# ifly_watch.net
KiCad netlist of a schematic drawn in Altium Designer
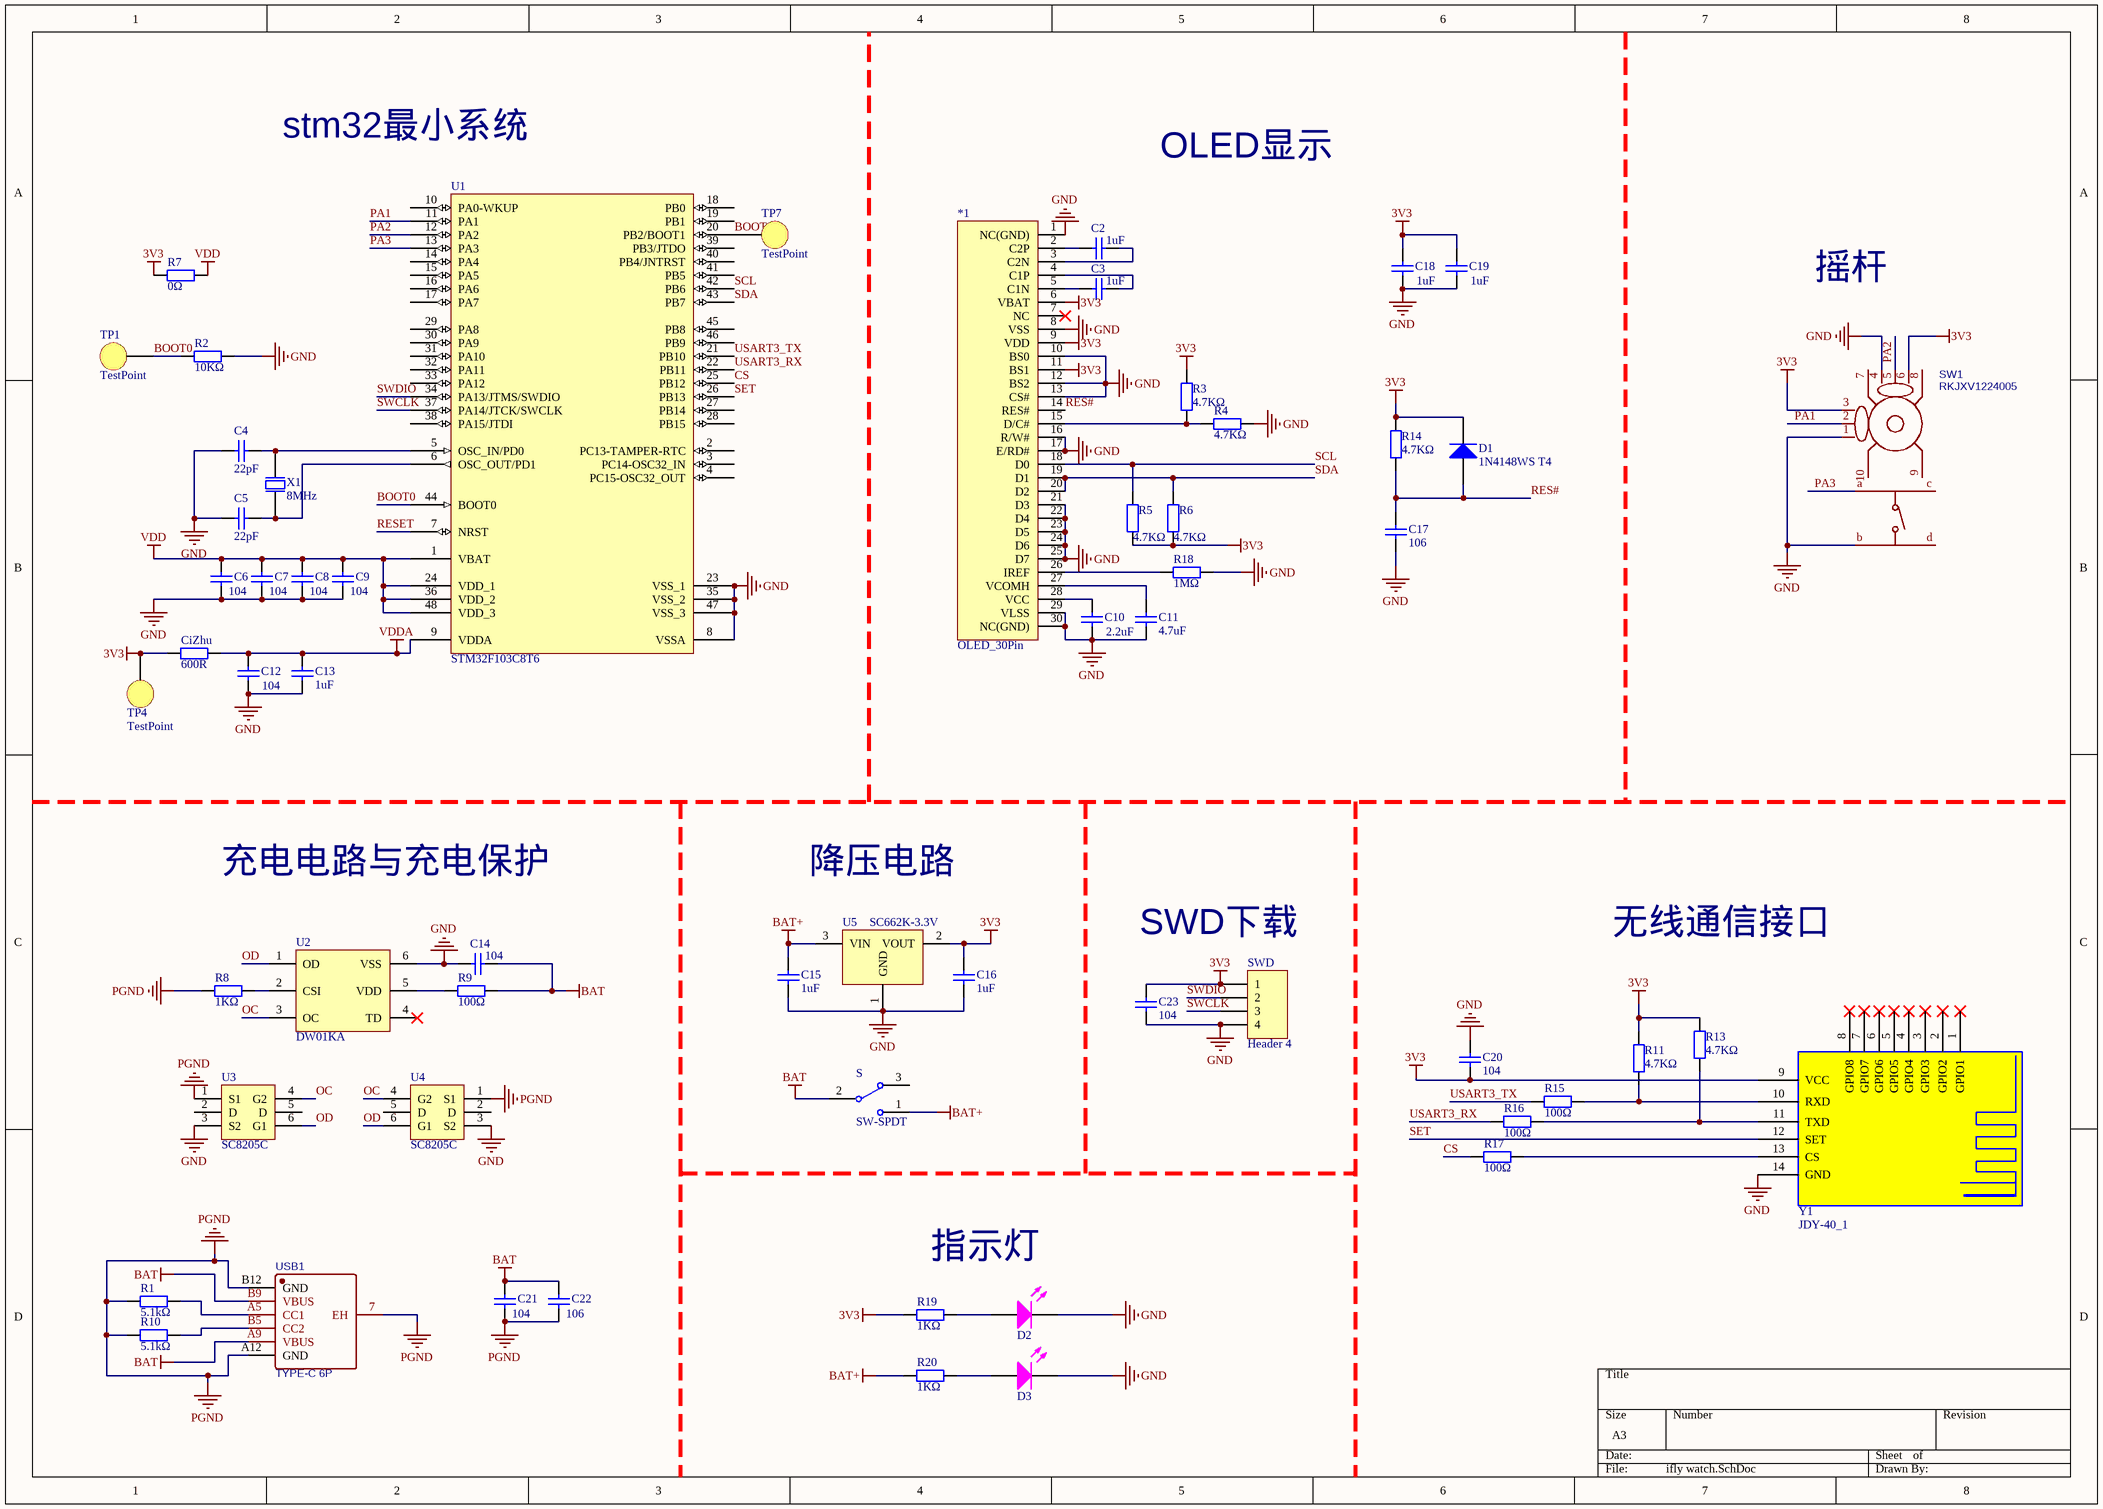
[diagram p0: ifly watch.SchDoc]

(export (version "E")
  (design (tool "Eeschema 10.0.6"))
  (components
    (comp (ref "*1")
      (value "OLED_30Pin")
      (footprint "OLED_0.96-30P-P0.70-12864")
      (libsource (lib "CQL_SchLib") (part "OLED_30Pin"))
    )
    (comp (ref "C2")
      (value "1uF")
      (footprint "LC-0603_C")
      (description "贴片电容")
      (libsource (lib "RobotLab") (part "0603 1uF (105) 10% 50V"))
    )
    (comp (ref "C3")
      (value "1uF")
      (footprint "LC-0603_C")
      (description "贴片电容")
      (libsource (lib "RobotLab") (part "0603 1uF (105) 10% 50V"))
    )
    (comp (ref "C4")
      (value "22pF")
      (footprint "C0603")
      (description "Polarized Capacitor (Radial)")
      (fields (field (name "Comment") "20pf") (field (name "PUBLISHER") "Altium Limited"))
      (libsource (lib "电容") (part "Cap Chip 0805"))
    )
    (comp (ref "C5")
      (value "22pF")
      (footprint "C0603")
      (description "Polarized Capacitor (Radial)")
      (fields (field (name "PUBLISHER") "Altium Limited"))
      (libsource (lib "电容") (part "Cap Chip 0805"))
    )
    (comp (ref "C6")
      (value "104")
      (footprint "LC-0603_C")
      (description "贴片电容")
      (libsource (lib "RobotLab") (part "0603 100nF (104) 10% 50V"))
    )
    (comp (ref "C7")
      (value "104")
      (footprint "LC-0603_C")
      (description "贴片电容")
      (libsource (lib "RobotLab") (part "0603 100nF (104) 10% 50V"))
    )
    (comp (ref "C8")
      (value "104")
      (footprint "LC-0603_C")
      (description "贴片电容")
      (libsource (lib "RobotLab") (part "0603 100nF (104) 10% 50V"))
    )
    (comp (ref "C9")
      (value "104")
      (footprint "LC-0603_C")
      (description "贴片电容")
      (libsource (lib "RobotLab") (part "0603 100nF (104) 10% 50V"))
    )
    (comp (ref "C10")
      (value "2.2uF")
      (footprint "LC-0603_C")
      (description "贴片电容")
      (libsource (lib "RobotLab") (part "0603 2.2uF (225) 10% 16V"))
    )
    (comp (ref "C11")
      (value "4.7uF")
      (footprint "LC-0603_C")
      (description "贴片电容")
      (libsource (lib "RobotLab") (part "0603 4.7uF (475) 10% 16V"))
    )
    (comp (ref "C12")
      (value "104")
      (footprint "LC-0603_C")
      (description "贴片电容")
      (libsource (lib "RobotLab") (part "0603 100nF (104) 10% 50V"))
    )
    (comp (ref "C13")
      (value "1uF")
      (footprint "LC-0603_C")
      (description "贴片电容")
      (libsource (lib "RobotLab") (part "0603 1uF (105) 10% 50V"))
    )
    (comp (ref "C14")
      (value "104")
      (footprint "LC-0603_C")
      (description "贴片电容")
      (libsource (lib "RobotLab") (part "0603 100nF (104) 10% 50V"))
    )
    (comp (ref "C15")
      (value "1uF")
      (footprint "LC-0603_C")
      (description "贴片电容")
      (libsource (lib "RobotLab") (part "0603 1uF (105) 10% 50V"))
    )
    (comp (ref "C16")
      (value "1uF")
      (footprint "LC-0603_C")
      (description "贴片电容")
      (libsource (lib "RobotLab") (part "0603 1uF (105) 10% 50V"))
    )
    (comp (ref "C17")
      (value "106")
      (footprint "LC-0603_C")
      (description "贴片电容")
      (libsource (lib "RobotLab") (part "0603 10uF (106) 10% 10V"))
    )
    (comp (ref "C18")
      (value "1uF")
      (footprint "LC-0603_C")
      (description "贴片电容")
      (libsource (lib "RobotLab") (part "0603 1uF (105) 10% 50V"))
    )
    (comp (ref "C19")
      (value "1uF")
      (footprint "LC-0603_C")
      (description "贴片电容")
      (libsource (lib "RobotLab") (part "0603 1uF (105) 10% 50V"))
    )
    (comp (ref "C20")
      (value "104")
      (footprint "LC-0603_C")
      (description "贴片电容")
      (libsource (lib "RobotLab") (part "0603 100nF (104) 10% 50V"))
    )
    (comp (ref "C21")
      (value "104")
      (footprint "LC-0603_C")
      (description "贴片电容")
      (libsource (lib "RobotLab") (part "0603 100nF (104) 10% 50V"))
    )
    (comp (ref "C22")
      (value "106")
      (footprint "LC-0603_C")
      (description "贴片电容")
      (libsource (lib "RobotLab") (part "0603 1uF (105) 10% 50V"))
    )
    (comp (ref "C23")
      (value "104")
      (footprint "LC-0603_C")
      (description "Polarized Capacitor (Radial)")
      (fields (field (name "PUBLISHER") "Altium Limited"))
      (libsource (lib "电容") (part "Cap Chip 0603"))
    )
    (comp (ref "CiZhu")
      (value "600R")
      (footprint "0603_R")
      (description "电阻_磁珠")
      (libsource (lib "CQL_SchLib") (part "Cizhu"))
    )
    (comp (ref "D1")
      (value "1N4148WS T4")
      (footprint "LC-SOD-323")
      (description "二极管")
      (libsource (lib "RobotLab") (part "SOD-323 1N4148WS T4"))
    )
    (comp (ref "D2")
      (value "0603")
      (footprint "LED0603 R")
      (description "Typical INFRARED GaAs LED")
      (fields (field (name "PUBLISHER") "Altium Limited"))
      (libsource (lib "光电显示器件") (part "LED-3-R"))
    )
    (comp (ref "D3")
      (value "0603")
      (footprint "LED0603 R")
      (description "Typical INFRARED GaAs LED")
      (fields (field (name "PUBLISHER") "Altium Limited"))
      (libsource (lib "光电显示器件") (part "LED-3-R"))
    )
    (comp (ref "R1")
      (value "5.1kΩ")
      (footprint "LC-0603_R")
      (description "贴片电阻")
      (libsource (lib "RobotLab") (part "0603 100Ω (1000) 1%"))
    )
    (comp (ref "R2")
      (value "10KΩ")
      (footprint "LC-0603_R")
      (description "贴片电阻")
      (libsource (lib "RobotLab") (part "0603 10KΩ (1002) 1%"))
    )
    (comp (ref "R3")
      (value "4.7KΩ")
      (footprint "LC-0603_R")
      (description "贴片电阻")
      (libsource (lib "") (part "0603 4.7KΩ (4701) 1%_2"))
    )
    (comp (ref "R4")
      (value "4.7KΩ")
      (footprint "LC-0603_R")
      (description "贴片电阻")
      (libsource (lib "") (part "0603 4.7KΩ (4701) 1%_1"))
    )
    (comp (ref "R5")
      (value "4.7KΩ")
      (footprint "LC-0603_R")
      (description "贴片电阻")
      (libsource (lib "") (part "0603 4.7KΩ (4701) 1%_2"))
    )
    (comp (ref "R6")
      (value "4.7KΩ")
      (footprint "LC-0603_R")
      (description "贴片电阻")
      (libsource (lib "") (part "0603 4.7KΩ (4701) 1%_2"))
    )
    (comp (ref "R7")
      (value "0Ω")
      (footprint "LC-0603_R")
      (description "贴片电阻")
      (libsource (lib "RobotLab") (part "0603 0Ω (0R0) 1%"))
    )
    (comp (ref "R8")
      (value "1KΩ")
      (footprint "LC-0603_R")
      (description "贴片电阻")
      (libsource (lib "RobotLab") (part "0603 1KΩ (1001) 1%"))
    )
    (comp (ref "R9")
      (value "100Ω")
      (footprint "LC-0603_R")
      (description "贴片电阻")
      (libsource (lib "RobotLab") (part "0603 100Ω (1000) 1%"))
    )
    (comp (ref "R10")
      (value "5.1kΩ")
      (footprint "LC-0603_R")
      (description "贴片电阻")
      (libsource (lib "RobotLab") (part "0603 100Ω (1000) 1%"))
    )
    (comp (ref "R11")
      (value "4.7KΩ")
      (footprint "LC-0603_R")
      (description "贴片电阻")
      (libsource (lib "RobotLab") (part "0603 4.7KΩ (4701) 1%"))
    )
    (comp (ref "R13")
      (value "4.7KΩ")
      (footprint "LC-0603_R")
      (description "贴片电阻")
      (libsource (lib "RobotLab") (part "0603 4.7KΩ (4701) 1%"))
    )
    (comp (ref "R14")
      (value "4.7KΩ")
      (footprint "LC-0603_R")
      (description "贴片电阻")
      (libsource (lib "") (part "0603 4.7KΩ (4701) 1%_2"))
    )
    (comp (ref "R15")
      (value "100Ω")
      (footprint "LC-0603_R")
      (description "贴片电阻")
      (libsource (lib "RobotLab") (part "0603 100Ω (1000) 1%"))
    )
    (comp (ref "R16")
      (value "100Ω")
      (footprint "LC-0603_R")
      (description "贴片电阻")
      (libsource (lib "RobotLab") (part "0603 100Ω (1000) 1%"))
    )
    (comp (ref "R17")
      (value "100Ω")
      (footprint "LC-0603_R")
      (description "贴片电阻")
      (libsource (lib "RobotLab") (part "0603 100Ω (1000) 1%"))
    )
    (comp (ref "R18")
      (value "1MΩ")
      (footprint "LC-0603_R")
      (description "贴片电阻")
      (libsource (lib "RobotLab") (part "0603 1MΩ (1004) 1%"))
    )
    (comp (ref "R19")
      (value "1KΩ")
      (footprint "LC-0603_R")
      (description "贴片电阻")
      (libsource (lib "RobotLab") (part "0603 1KΩ (1001) 1%"))
    )
    (comp (ref "R20")
      (value "1KΩ")
      (footprint "LC-0603_R")
      (description "贴片电阻")
      (libsource (lib "RobotLab") (part "0603 1KΩ (1001) 1%"))
    )
    (comp (ref "S")
      (value "SW-SPDT")
      (footprint "version3:8.5*3.5_3P")
      (description "SPDT Subminiature Toggle Switch, Right Angle Mounting, Vertical Actuation")
      (fields (field (name "PUBLISHER") "Altium Limited"))
      (libsource (lib "开关按键器件") (part "SW-SPDT"))
    )
    (comp (ref "SW1")
      (value "RKJXV1224005")
      (footprint "RKJXV1224005")
      (fields (field (name "BOM_SUPPLIER PART") "C146170") (field (name "CONTRIBUTOR") "LCSC"))
      (libsource (lib "mySchlib") (part "RKJXV1224005"))
    )
    (comp (ref "SWD")
      (value "Header 4")
      (footprint "HDR1X4")
      (description "Header, 4-Pin")
      (fields (field (name "PUBLISHER") "Altium Limited"))
      (libsource (lib "Miscellaneous Connectors") (part "Header 4"))
    )
    (comp (ref "TP1")
      (value "TestPoint")
      (footprint "TestPoint")
      (libsource (lib "CQL_SchLib") (part "TestPoint"))
    )
    (comp (ref "TP4")
      (value "TestPoint")
      (footprint "TestPoint")
      (libsource (lib "CQL_SchLib") (part "TestPoint"))
    )
    (comp (ref "TP7")
      (value "TestPoint")
      (footprint "TestPoint")
      (libsource (lib "CQL_SchLib") (part "TestPoint"))
    )
    (comp (ref "U1")
      (value "STM32F103C8T6")
      (footprint "LC-LQFP-48_7x7x05P")
      (description "STM32 ARM-based 32-bit MCU with 64 Kbytes Flash, 48-pin LQFP, Industrial Temperature")
      (fields (field (name "PUBLISHER") "*"))
      (libsource (lib "ST MCU元件库") (part "STM32F103C8T6"))
    )
    (comp (ref "U2")
      (value "DW01KA")
      (footprint "SOT-23-6")
      (description "锂电池保护芯片")
      (libsource (lib "CQL_SchLib") (part "DW01KA"))
    )
    (comp (ref "U3")
      (value "SC8205C")
      (footprint "SOT-23-6")
      (description "二合一MOS")
      (libsource (lib "CQL_SchLib") (part "SC8205C"))
    )
    (comp (ref "U4")
      (value "SC8205C")
      (footprint "SOT-23-6")
      (description "二合一MOS")
      (libsource (lib "") (part "SC8205C_1"))
    )
    (comp (ref "U5")
      (value "SC662K-3.3V")
      (footprint "SOT-23-3L")
      (description "LDO")
      (libsource (lib "MyPCB") (part "SC662K-3.3V"))
    )
    (comp (ref "USB1")
      (value "TYPE-C 6P")
      (footprint "TYPE-C-SMD_TYPE-C-6P")
      (fields (field (name "BOM_SUPPLIER PART") "C456012") (field (name "CONTRIBUTOR") "LCSC"))
      (libsource (lib "mySchlib") (part "TYPE-C 6P"))
    )
    (comp (ref "X1")
      (value "5032")
      (footprint "SMD5032-2")
      (description "Crystal Oscillator")
      (fields (field (name "FREQUENCY") "8MHz") (field (name "PUBLISHER") "Altium Limited"))
      (libsource (lib "蜂鸣器 咪头 保险丝 电池 晶振") (part "XTAL"))
    )
    (comp (ref "Y1")
      (value "JDY-40_1")
      (footprint "JDY-401 -No via")
      (description "串口透传无过孔")
      (libsource (lib "CQL_SchLib") (part "JDY-40_1"))
    )
  )
  (nets
    (net (code "1") (name "/BOOT0") (class "Default")
      (node (ref "R2") (pin "2") (pinfunction "2_2") (pintype "passive"))
      (node (ref "TP1") (pin "1") (pinfunction "TestPoint_1") (pintype "passive"))
      (node (ref "U1") (pin "44") (pinfunction "BOOT0_44") (pintype "input"))
    )
    (net (code "2") (name "/BOOT1") (class "Default")
      (node (ref "TP7") (pin "1") (pinfunction "TestPoint_1") (pintype "passive"))
      (node (ref "U1") (pin "20") (pinfunction "PB2/BOOT1_20") (pintype "bidirectional"))
    )
    (net (code "3") (name "/CS") (class "Default")
      (node (ref "R17") (pin "1") (pinfunction "1_1") (pintype "passive"))
      (node (ref "U1") (pin "25") (pinfunction "PB12_25") (pintype "bidirectional"))
    )
    (net (code "4") (name "/OC") (class "Default")
      (node (ref "U2") (pin "3") (pinfunction "OC_3") (pintype "passive"))
      (node (ref "U3") (pin "4") (pinfunction "G2_4") (pintype "passive"))
      (node (ref "U4") (pin "4") (pinfunction "G2_4") (pintype "passive"))
    )
    (net (code "5") (name "/OD") (class "Default")
      (node (ref "U2") (pin "1") (pinfunction "OD_1") (pintype "passive"))
      (node (ref "U3") (pin "6") (pinfunction "G1_6") (pintype "passive"))
      (node (ref "U4") (pin "6") (pinfunction "G1_6") (pintype "passive"))
    )
    (net (code "6") (name "/PA1") (class "Default")
      (node (ref "SW1") (pin "2") (pinfunction "DTA_2") (pintype "passive"))
      (node (ref "U1") (pin "11") (pinfunction "PA1_11") (pintype "bidirectional"))
    )
    (net (code "7") (name "/PA2") (class "Default")
      (node (ref "SW1") (pin "5") (pinfunction "DTA_5") (pintype "passive"))
      (node (ref "U1") (pin "12") (pinfunction "PA2_12") (pintype "bidirectional"))
    )
    (net (code "8") (name "/PA3") (class "Default")
      (node (ref "SW1") (pin "a") (pinfunction "a_a") (pintype "passive"))
      (node (ref "U1") (pin "13") (pinfunction "PA3_13") (pintype "bidirectional"))
    )
    (net (code "9") (name "/RES#") (class "Default")
      (node (ref "*1") (pin "14") (pinfunction "RES#_14") (pintype "passive"))
      (node (ref "C17") (pin "2") (pinfunction "2_2") (pintype "passive"))
      (node (ref "D1") (pin "1") (pinfunction "A_1") (pintype "passive"))
      (node (ref "R14") (pin "1") (pinfunction "1_1") (pintype "passive"))
    )
    (net (code "10") (name "/RESET") (class "Default")
      (node (ref "U1") (pin "7") (pinfunction "NRST_7") (pintype "bidirectional"))
    )
    (net (code "11") (name "/SCL") (class "Default")
      (node (ref "*1") (pin "18") (pinfunction "D0_18") (pintype "passive"))
      (node (ref "R5") (pin "2") (pinfunction "2_2") (pintype "passive"))
      (node (ref "U1") (pin "42") (pinfunction "PB6_42") (pintype "bidirectional"))
    )
    (net (code "12") (name "/SDA") (class "Default")
      (node (ref "*1") (pin "19") (pinfunction "D1_19") (pintype "passive"))
      (node (ref "*1") (pin "20") (pinfunction "D2_20") (pintype "passive"))
      (node (ref "R6") (pin "2") (pinfunction "2_2") (pintype "passive"))
      (node (ref "U1") (pin "43") (pinfunction "PB7_43") (pintype "bidirectional"))
    )
    (net (code "13") (name "/SET") (class "Default")
      (node (ref "U1") (pin "26") (pinfunction "PB13_26") (pintype "bidirectional"))
      (node (ref "Y1") (pin "12") (pinfunction "SET_12") (pintype "passive"))
    )
    (net (code "14") (name "/SWCLK") (class "Default")
      (node (ref "SWD") (pin "3") (pinfunction "3_3") (pintype "passive"))
      (node (ref "U1") (pin "37") (pinfunction "PA14/JTCK/SWCLK_37") (pintype "bidirectional"))
    )
    (net (code "15") (name "/SWDIO") (class "Default")
      (node (ref "SWD") (pin "2") (pinfunction "2_2") (pintype "passive"))
      (node (ref "U1") (pin "34") (pinfunction "PA13/JTMS/SWDIO_34") (pintype "bidirectional"))
    )
    (net (code "16") (name "/USART3_RX") (class "Default")
      (node (ref "R16") (pin "1") (pinfunction "1_1") (pintype "passive"))
      (node (ref "U1") (pin "22") (pinfunction "PB11_22") (pintype "bidirectional"))
    )
    (net (code "17") (name "/USART3_TX") (class "Default")
      (node (ref "R15") (pin "1") (pinfunction "1_1") (pintype "passive"))
      (node (ref "U1") (pin "21") (pinfunction "PB10_21") (pintype "bidirectional"))
    )
    (net (code "18") (name "3V3") (class "Default")
      (node (ref "*1") (pin "11") (pinfunction "BS1_11") (pintype "passive"))
      (node (ref "*1") (pin "6") (pinfunction "VBAT_6") (pintype "passive"))
      (node (ref "*1") (pin "9") (pinfunction "VDD_9") (pintype "passive"))
      (node (ref "C16") (pin "2") (pinfunction "2_2") (pintype "passive"))
      (node (ref "C18") (pin "2") (pinfunction "2_2") (pintype "passive"))
      (node (ref "C19") (pin "2") (pinfunction "2_2") (pintype "passive"))
      (node (ref "C20") (pin "2") (pinfunction "2_2") (pintype "passive"))
      (node (ref "C23") (pin "2") (pinfunction "2_2") (pintype "passive"))
      (node (ref "CiZhu") (pin "1") (pinfunction "1_1") (pintype "passive"))
      (node (ref "D1") (pin "2") (pinfunction "K_2") (pintype "passive"))
      (node (ref "R11") (pin "1") (pinfunction "1_1") (pintype "passive"))
      (node (ref "R13") (pin "1") (pinfunction "1_1") (pintype "passive"))
      (node (ref "R14") (pin "2") (pinfunction "2_2") (pintype "passive"))
      (node (ref "R19") (pin "1") (pinfunction "1_1") (pintype "passive"))
      (node (ref "R3") (pin "2") (pinfunction "2_2") (pintype "passive"))
      (node (ref "R5") (pin "1") (pinfunction "1_1") (pintype "passive"))
      (node (ref "R6") (pin "1") (pinfunction "1_1") (pintype "passive"))
      (node (ref "R7") (pin "2") (pinfunction "2_2") (pintype "passive"))
      (node (ref "SW1") (pin "3") (pinfunction "A_3") (pintype "passive"))
      (node (ref "SW1") (pin "6") (pinfunction "B_6") (pintype "passive"))
      (node (ref "SWD") (pin "1") (pinfunction "1_1") (pintype "passive"))
      (node (ref "TP4") (pin "1") (pinfunction "TestPoint_1") (pintype "passive"))
      (node (ref "U5") (pin "2") (pinfunction "VOUT_2") (pintype "passive"))
      (node (ref "Y1") (pin "9") (pinfunction "VCC_9") (pintype "passive"))
    )
    (net (code "19") (name "BAT") (class "Default")
      (node (ref "C14") (pin "1") (pinfunction "1_1") (pintype "passive"))
      (node (ref "C21") (pin "1") (pinfunction "1_1") (pintype "passive"))
      (node (ref "C22") (pin "2") (pinfunction "2_2") (pintype "passive"))
      (node (ref "R9") (pin "2") (pinfunction "2_2") (pintype "passive"))
      (node (ref "S") (pin "2") (pintype "passive"))
      (node (ref "USB1") (pin "A9") (pinfunction "VBUS_A9") (pintype "passive"))
      (node (ref "USB1") (pin "B9") (pinfunction "VBUS_B9") (pintype "passive"))
    )
    (net (code "20") (name "BAT+") (class "Default")
      (node (ref "C15") (pin "2") (pinfunction "2_2") (pintype "passive"))
      (node (ref "R20") (pin "1") (pinfunction "1_1") (pintype "passive"))
      (node (ref "S") (pin "1") (pintype "passive"))
      (node (ref "U5") (pin "3") (pinfunction "VIN_3") (pintype "passive"))
    )
    (net (code "21") (name "GND") (class "Default")
      (node (ref "*1") (pin "1") (pinfunction "NC(GND)_1") (pintype "passive"))
      (node (ref "*1") (pin "10") (pinfunction "BS0_10") (pintype "passive"))
      (node (ref "*1") (pin "12") (pinfunction "BS2_12") (pintype "passive"))
      (node (ref "*1") (pin "13") (pinfunction "CS#_13") (pintype "passive"))
      (node (ref "*1") (pin "16") (pinfunction "R/W#_16") (pintype "passive"))
      (node (ref "*1") (pin "17") (pinfunction "E/RD#_17") (pintype "passive"))
      (node (ref "*1") (pin "21") (pinfunction "D3_21") (pintype "passive"))
      (node (ref "*1") (pin "22") (pinfunction "D4_22") (pintype "passive"))
      (node (ref "*1") (pin "23") (pinfunction "D5_23") (pintype "passive"))
      (node (ref "*1") (pin "24") (pinfunction "D6_24") (pintype "passive"))
      (node (ref "*1") (pin "25") (pinfunction "D7_25") (pintype "passive"))
      (node (ref "*1") (pin "29") (pinfunction "VLSS_29") (pintype "passive"))
      (node (ref "*1") (pin "30") (pinfunction "NC(GND)_30") (pintype "passive"))
      (node (ref "*1") (pin "8") (pinfunction "VSS_8") (pintype "passive"))
      (node (ref "C10") (pin "1") (pinfunction "1_1") (pintype "passive"))
      (node (ref "C11") (pin "1") (pinfunction "1_1") (pintype "passive"))
      (node (ref "C12") (pin "1") (pinfunction "1_1") (pintype "passive"))
      (node (ref "C13") (pin "1") (pinfunction "1_1") (pintype "passive"))
      (node (ref "C14") (pin "2") (pinfunction "2_2") (pintype "passive"))
      (node (ref "C15") (pin "1") (pinfunction "1_1") (pintype "passive"))
      (node (ref "C16") (pin "1") (pinfunction "1_1") (pintype "passive"))
      (node (ref "C17") (pin "1") (pinfunction "1_1") (pintype "passive"))
      (node (ref "C18") (pin "1") (pinfunction "1_1") (pintype "passive"))
      (node (ref "C19") (pin "1") (pinfunction "1_1") (pintype "passive"))
      (node (ref "C20") (pin "1") (pinfunction "1_1") (pintype "passive"))
      (node (ref "C23") (pin "1") (pinfunction "1_1") (pintype "passive"))
      (node (ref "C4") (pin "1") (pinfunction "1_1") (pintype "passive"))
      (node (ref "C5") (pin "1") (pinfunction "1_1") (pintype "passive"))
      (node (ref "C6") (pin "1") (pinfunction "1_1") (pintype "passive"))
      (node (ref "C7") (pin "1") (pinfunction "1_1") (pintype "passive"))
      (node (ref "C8") (pin "1") (pinfunction "1_1") (pintype "passive"))
      (node (ref "C9") (pin "1") (pinfunction "1_1") (pintype "passive"))
      (node (ref "D2") (pin "2") (pinfunction "K_2") (pintype "passive"))
      (node (ref "D3") (pin "2") (pinfunction "K_2") (pintype "passive"))
      (node (ref "R18") (pin "2") (pinfunction "2_2") (pintype "passive"))
      (node (ref "R2") (pin "1") (pinfunction "1_1") (pintype "passive"))
      (node (ref "R4") (pin "1") (pinfunction "1_1") (pintype "passive"))
      (node (ref "SW1") (pin "1") (pinfunction "B_1") (pintype "passive"))
      (node (ref "SW1") (pin "4") (pinfunction "A_4") (pintype "passive"))
      (node (ref "SW1") (pin "b") (pinfunction "b_b") (pintype "passive"))
      (node (ref "SWD") (pin "4") (pinfunction "4_4") (pintype "passive"))
      (node (ref "U1") (pin "23") (pinfunction "VSS_1_23") (pintype "power_in"))
      (node (ref "U1") (pin "35") (pinfunction "VSS_2_35") (pintype "power_in"))
      (node (ref "U1") (pin "47") (pinfunction "VSS_3_47") (pintype "power_in"))
      (node (ref "U1") (pin "8") (pinfunction "VSSA_8") (pintype "power_in"))
      (node (ref "U2") (pin "6") (pinfunction "VSS_6") (pintype "passive"))
      (node (ref "U3") (pin "3") (pinfunction "S2_3") (pintype "passive"))
      (node (ref "U4") (pin "3") (pinfunction "S2_3") (pintype "passive"))
      (node (ref "U5") (pin "1") (pinfunction "GND_1") (pintype "passive"))
      (node (ref "Y1") (pin "14") (pinfunction "GND_14") (pintype "passive"))
    )
    (net (code "22") (name "Net-(*1-C1N)") (class "Default")
      (node (ref "*1") (pin "5") (pinfunction "C1N_5") (pintype "passive"))
      (node (ref "C3") (pin "2") (pinfunction "2_2") (pintype "passive"))
    )
    (net (code "23") (name "Net-(*1-C1P)") (class "Default")
      (node (ref "*1") (pin "4") (pinfunction "C1P_4") (pintype "passive"))
      (node (ref "C3") (pin "1") (pinfunction "1_1") (pintype "passive"))
    )
    (net (code "24") (name "Net-(*1-C2N)") (class "Default")
      (node (ref "*1") (pin "3") (pinfunction "C2N_3") (pintype "passive"))
      (node (ref "C2") (pin "1") (pinfunction "1_1") (pintype "passive"))
    )
    (net (code "25") (name "Net-(*1-C2P)") (class "Default")
      (node (ref "*1") (pin "2") (pinfunction "C2P_2") (pintype "passive"))
      (node (ref "C2") (pin "2") (pinfunction "2_2") (pintype "passive"))
    )
    (net (code "26") (name "Net-(*1-D{slash}C#)") (class "Default")
      (node (ref "*1") (pin "15") (pinfunction "D/C#_15") (pintype "passive"))
      (node (ref "R3") (pin "1") (pinfunction "1_1") (pintype "passive"))
      (node (ref "R4") (pin "2") (pinfunction "2_2") (pintype "passive"))
    )
    (net (code "27") (name "Net-(*1-IREF)") (class "Default")
      (node (ref "*1") (pin "26") (pinfunction "IREF_26") (pintype "passive"))
      (node (ref "R18") (pin "1") (pinfunction "1_1") (pintype "passive"))
    )
    (net (code "28") (name "Net-(*1-VCC)") (class "Default")
      (node (ref "*1") (pin "28") (pinfunction "VCC_28") (pintype "passive"))
      (node (ref "C10") (pin "2") (pinfunction "2_2") (pintype "passive"))
    )
    (net (code "29") (name "Net-(*1-VCOMH)") (class "Default")
      (node (ref "*1") (pin "27") (pinfunction "VCOMH_27") (pintype "passive"))
      (node (ref "C11") (pin "2") (pinfunction "2_2") (pintype "passive"))
    )
    (net (code "30") (name "Net-(D2-A)") (class "Default")
      (node (ref "D2") (pin "1") (pinfunction "A_1") (pintype "passive"))
      (node (ref "R19") (pin "2") (pinfunction "2_2") (pintype "passive"))
    )
    (net (code "31") (name "Net-(D3-A)") (class "Default")
      (node (ref "D3") (pin "1") (pinfunction "A_1") (pintype "passive"))
      (node (ref "R20") (pin "2") (pinfunction "2_2") (pintype "passive"))
    )
    (net (code "32") (name "Net-(U1-OSC_IN{slash}PD0)") (class "Default")
      (node (ref "C4") (pin "2") (pinfunction "2_2") (pintype "passive"))
      (node (ref "U1") (pin "5") (pinfunction "OSC_IN/PD0_5") (pintype "input"))
      (node (ref "X1") (pin "2") (pinfunction "OSC2_2") (pintype "passive"))
    )
    (net (code "33") (name "Net-(U1-OSC_OUT{slash}PD1)") (class "Default")
      (node (ref "C5") (pin "2") (pinfunction "2_2") (pintype "passive"))
      (node (ref "U1") (pin "6") (pinfunction "OSC_OUT/PD1_6") (pintype "output"))
      (node (ref "X1") (pin "1") (pinfunction "OSC1_1") (pintype "passive"))
    )
    (net (code "34") (name "Net-(U2-CSI)") (class "Default")
      (node (ref "R8") (pin "2") (pinfunction "2_2") (pintype "passive"))
      (node (ref "U2") (pin "2") (pinfunction "CSI_2") (pintype "passive"))
    )
    (net (code "35") (name "Net-(U2-VDD)") (class "Default")
      (node (ref "R9") (pin "1") (pinfunction "1_1") (pintype "passive"))
      (node (ref "U2") (pin "5") (pinfunction "VDD_5") (pintype "passive"))
    )
    (net (code "36") (name "Net-(USB1-CC1)") (class "Default")
      (node (ref "R1") (pin "2") (pinfunction "2_2") (pintype "passive"))
      (node (ref "USB1") (pin "A5") (pinfunction "CC1_A5") (pintype "passive"))
    )
    (net (code "37") (name "Net-(USB1-CC2)") (class "Default")
      (node (ref "R10") (pin "2") (pinfunction "2_2") (pintype "passive"))
      (node (ref "USB1") (pin "B5") (pinfunction "CC2_B5") (pintype "passive"))
    )
    (net (code "38") (name "Net-(Y1-CS)") (class "Default")
      (node (ref "R17") (pin "2") (pinfunction "2_2") (pintype "passive"))
      (node (ref "Y1") (pin "13") (pinfunction "CS_13") (pintype "passive"))
    )
    (net (code "39") (name "Net-(Y1-RXD)") (class "Default")
      (node (ref "R11") (pin "2") (pinfunction "2_2") (pintype "passive"))
      (node (ref "R15") (pin "2") (pinfunction "2_2") (pintype "passive"))
      (node (ref "Y1") (pin "10") (pinfunction "RXD_10") (pintype "passive"))
    )
    (net (code "40") (name "Net-(Y1-TXD)") (class "Default")
      (node (ref "R13") (pin "2") (pinfunction "2_2") (pintype "passive"))
      (node (ref "R16") (pin "2") (pinfunction "2_2") (pintype "passive"))
      (node (ref "Y1") (pin "11") (pinfunction "TXD_11") (pintype "passive"))
    )
    (net (code "41") (name "PGND") (class "Default")
      (node (ref "C21") (pin "2") (pinfunction "2_2") (pintype "passive"))
      (node (ref "C22") (pin "1") (pinfunction "1_1") (pintype "passive"))
      (node (ref "R1") (pin "1") (pinfunction "1_1") (pintype "passive"))
      (node (ref "R10") (pin "1") (pinfunction "1_1") (pintype "passive"))
      (node (ref "R8") (pin "1") (pinfunction "1_1") (pintype "passive"))
      (node (ref "U3") (pin "1") (pinfunction "S1_1") (pintype "passive"))
      (node (ref "U4") (pin "1") (pinfunction "S1_1") (pintype "passive"))
      (node (ref "USB1") (pin "7") (pinfunction "EH_7") (pintype "passive"))
      (node (ref "USB1") (pin "A12") (pinfunction "GND_A12") (pintype "passive"))
      (node (ref "USB1") (pin "B12") (pinfunction "GND_B12") (pintype "passive"))
    )
    (net (code "42") (name "VDD") (class "Default")
      (node (ref "C6") (pin "2") (pinfunction "2_2") (pintype "passive"))
      (node (ref "C7") (pin "2") (pinfunction "2_2") (pintype "passive"))
      (node (ref "C8") (pin "2") (pinfunction "2_2") (pintype "passive"))
      (node (ref "C9") (pin "2") (pinfunction "2_2") (pintype "passive"))
      (node (ref "R7") (pin "1") (pinfunction "1_1") (pintype "passive"))
      (node (ref "U1") (pin "1") (pinfunction "VBAT_1") (pintype "power_in"))
      (node (ref "U1") (pin "24") (pinfunction "VDD_1_24") (pintype "power_in"))
      (node (ref "U1") (pin "36") (pinfunction "VDD_2_36") (pintype "power_in"))
      (node (ref "U1") (pin "48") (pinfunction "VDD_3_48") (pintype "power_in"))
    )
    (net (code "43") (name "VDDA") (class "Default")
      (node (ref "C12") (pin "2") (pinfunction "2_2") (pintype "passive"))
      (node (ref "C13") (pin "2") (pinfunction "2_2") (pintype "passive"))
      (node (ref "CiZhu") (pin "2") (pinfunction "2_2") (pintype "passive"))
      (node (ref "U1") (pin "9") (pinfunction "VDDA_9") (pintype "power_in"))
    )
    (net (code "44") (name "unconnected-(*1-NC-Pad7)") (class "Default")
      (node (ref "*1") (pin "7") (pinfunction "NC_7") (pintype "passive+no_connect"))
    )
    (net (code "45") (name "unconnected-(S-Pad3)") (class "Default")
      (node (ref "S") (pin "3") (pintype "passive"))
    )
    (net (code "46") (name "unconnected-(SW1-GND-Pad7)") (class "Default")
      (node (ref "SW1") (pin "7") (pinfunction "GND_7") (pintype "passive"))
    )
    (net (code "47") (name "unconnected-(SW1-GND-Pad8)") (class "Default")
      (node (ref "SW1") (pin "8") (pinfunction "GND_8") (pintype "passive"))
    )
    (net (code "48") (name "unconnected-(SW1-GND-Pad9)") (class "Default")
      (node (ref "SW1") (pin "9") (pinfunction "GND_9") (pintype "passive"))
    )
    (net (code "49") (name "unconnected-(SW1-GND-Pad10)") (class "Default")
      (node (ref "SW1") (pin "10") (pinfunction "GND_10") (pintype "passive"))
    )
    (net (code "50") (name "unconnected-(SW1-Padc)") (class "Default")
      (node (ref "SW1") (pin "c") (pinfunction "c_c") (pintype "passive"))
    )
    (net (code "51") (name "unconnected-(SW1-Padd)") (class "Default")
      (node (ref "SW1") (pin "d") (pinfunction "d_d") (pintype "passive"))
    )
    (net (code "52") (name "unconnected-(U1-PA0-WKUP-Pad10)") (class "Default")
      (node (ref "U1") (pin "10") (pinfunction "PA0-WKUP_10") (pintype "bidirectional"))
    )
    (net (code "53") (name "unconnected-(U1-PA4-Pad14)") (class "Default")
      (node (ref "U1") (pin "14") (pinfunction "PA4_14") (pintype "bidirectional"))
    )
    (net (code "54") (name "unconnected-(U1-PA5-Pad15)") (class "Default")
      (node (ref "U1") (pin "15") (pinfunction "PA5_15") (pintype "bidirectional"))
    )
    (net (code "55") (name "unconnected-(U1-PA6-Pad16)") (class "Default")
      (node (ref "U1") (pin "16") (pinfunction "PA6_16") (pintype "bidirectional"))
    )
    (net (code "56") (name "unconnected-(U1-PA7-Pad17)") (class "Default")
      (node (ref "U1") (pin "17") (pinfunction "PA7_17") (pintype "bidirectional"))
    )
    (net (code "57") (name "unconnected-(U1-PA8-Pad29)") (class "Default")
      (node (ref "U1") (pin "29") (pinfunction "PA8_29") (pintype "bidirectional"))
    )
    (net (code "58") (name "unconnected-(U1-PA9-Pad30)") (class "Default")
      (node (ref "U1") (pin "30") (pinfunction "PA9_30") (pintype "bidirectional"))
    )
    (net (code "59") (name "unconnected-(U1-PA10-Pad31)") (class "Default")
      (node (ref "U1") (pin "31") (pinfunction "PA10_31") (pintype "bidirectional"))
    )
    (net (code "60") (name "unconnected-(U1-PA11-Pad32)") (class "Default")
      (node (ref "U1") (pin "32") (pinfunction "PA11_32") (pintype "bidirectional"))
    )
    (net (code "61") (name "unconnected-(U1-PA12-Pad33)") (class "Default")
      (node (ref "U1") (pin "33") (pinfunction "PA12_33") (pintype "bidirectional"))
    )
    (net (code "62") (name "unconnected-(U1-PA15{slash}JTDI-Pad38)") (class "Default")
      (node (ref "U1") (pin "38") (pinfunction "PA15/JTDI_38") (pintype "bidirectional"))
    )
    (net (code "63") (name "unconnected-(U1-PB0-Pad18)") (class "Default")
      (node (ref "U1") (pin "18") (pinfunction "PB0_18") (pintype "bidirectional"))
    )
    (net (code "64") (name "unconnected-(U1-PB1-Pad19)") (class "Default")
      (node (ref "U1") (pin "19") (pinfunction "PB1_19") (pintype "bidirectional"))
    )
    (net (code "65") (name "unconnected-(U1-PB3{slash}JTDO-Pad39)") (class "Default")
      (node (ref "U1") (pin "39") (pinfunction "PB3/JTDO_39") (pintype "bidirectional"))
    )
    (net (code "66") (name "unconnected-(U1-PB4{slash}JNTRST-Pad40)") (class "Default")
      (node (ref "U1") (pin "40") (pinfunction "PB4/JNTRST_40") (pintype "bidirectional"))
    )
    (net (code "67") (name "unconnected-(U1-PB5-Pad41)") (class "Default")
      (node (ref "U1") (pin "41") (pinfunction "PB5_41") (pintype "bidirectional"))
    )
    (net (code "68") (name "unconnected-(U1-PB8-Pad45)") (class "Default")
      (node (ref "U1") (pin "45") (pinfunction "PB8_45") (pintype "bidirectional"))
    )
    (net (code "69") (name "unconnected-(U1-PB9-Pad46)") (class "Default")
      (node (ref "U1") (pin "46") (pinfunction "PB9_46") (pintype "bidirectional"))
    )
    (net (code "70") (name "unconnected-(U1-PB14-Pad27)") (class "Default")
      (node (ref "U1") (pin "27") (pinfunction "PB14_27") (pintype "bidirectional"))
    )
    (net (code "71") (name "unconnected-(U1-PB15-Pad28)") (class "Default")
      (node (ref "U1") (pin "28") (pinfunction "PB15_28") (pintype "bidirectional"))
    )
    (net (code "72") (name "unconnected-(U1-PC13-TAMPER-RTC-Pad2)") (class "Default")
      (node (ref "U1") (pin "2") (pinfunction "PC13-TAMPER-RTC_2") (pintype "bidirectional"))
    )
    (net (code "73") (name "unconnected-(U1-PC14-OSC32_IN-Pad3)") (class "Default")
      (node (ref "U1") (pin "3") (pinfunction "PC14-OSC32_IN_3") (pintype "bidirectional"))
    )
    (net (code "74") (name "unconnected-(U1-PC15-OSC32_OUT-Pad4)") (class "Default")
      (node (ref "U1") (pin "4") (pinfunction "PC15-OSC32_OUT_4") (pintype "bidirectional"))
    )
    (net (code "75") (name "unconnected-(U2-TD-Pad4)") (class "Default")
      (node (ref "U2") (pin "4") (pinfunction "TD_4") (pintype "passive+no_connect"))
    )
    (net (code "76") (name "unconnected-(U3-D-Pad2)") (class "Default")
      (node (ref "U3") (pin "2") (pinfunction "D_2") (pintype "passive"))
    )
    (net (code "77") (name "unconnected-(U3-D-Pad5)") (class "Default")
      (node (ref "U3") (pin "5") (pinfunction "D_5") (pintype "passive"))
    )
    (net (code "78") (name "unconnected-(U4-D-Pad2)") (class "Default")
      (node (ref "U4") (pin "2") (pinfunction "D_2") (pintype "passive"))
    )
    (net (code "79") (name "unconnected-(U4-D-Pad5)") (class "Default")
      (node (ref "U4") (pin "5") (pinfunction "D_5") (pintype "passive"))
    )
    (net (code "80") (name "unconnected-(Y1-GPIO1-Pad1)") (class "Default")
      (node (ref "Y1") (pin "1") (pinfunction "GPIO1_1") (pintype "passive+no_connect"))
    )
    (net (code "81") (name "unconnected-(Y1-GPIO2-Pad2)") (class "Default")
      (node (ref "Y1") (pin "2") (pinfunction "GPIO2_2") (pintype "passive+no_connect"))
    )
    (net (code "82") (name "unconnected-(Y1-GPIO3-Pad3)") (class "Default")
      (node (ref "Y1") (pin "3") (pinfunction "GPIO3_3") (pintype "passive+no_connect"))
    )
    (net (code "83") (name "unconnected-(Y1-GPIO4-Pad4)") (class "Default")
      (node (ref "Y1") (pin "4") (pinfunction "GPIO4_4") (pintype "passive+no_connect"))
    )
    (net (code "84") (name "unconnected-(Y1-GPIO5-Pad5)") (class "Default")
      (node (ref "Y1") (pin "5") (pinfunction "GPIO5_5") (pintype "passive+no_connect"))
    )
    (net (code "85") (name "unconnected-(Y1-GPIO6-Pad6)") (class "Default")
      (node (ref "Y1") (pin "6") (pinfunction "GPIO6_6") (pintype "passive+no_connect"))
    )
    (net (code "86") (name "unconnected-(Y1-GPIO7-Pad7)") (class "Default")
      (node (ref "Y1") (pin "7") (pinfunction "GPIO7_7") (pintype "passive+no_connect"))
    )
    (net (code "87") (name "unconnected-(Y1-GPIO8-Pad8)") (class "Default")
      (node (ref "Y1") (pin "8") (pinfunction "GPIO8_8") (pintype "passive+no_connect"))
    )
  )
)
